# SCH_cansat2025_2025-10-27.net
KiCad netlist of a schematic drawn in EasyEDA
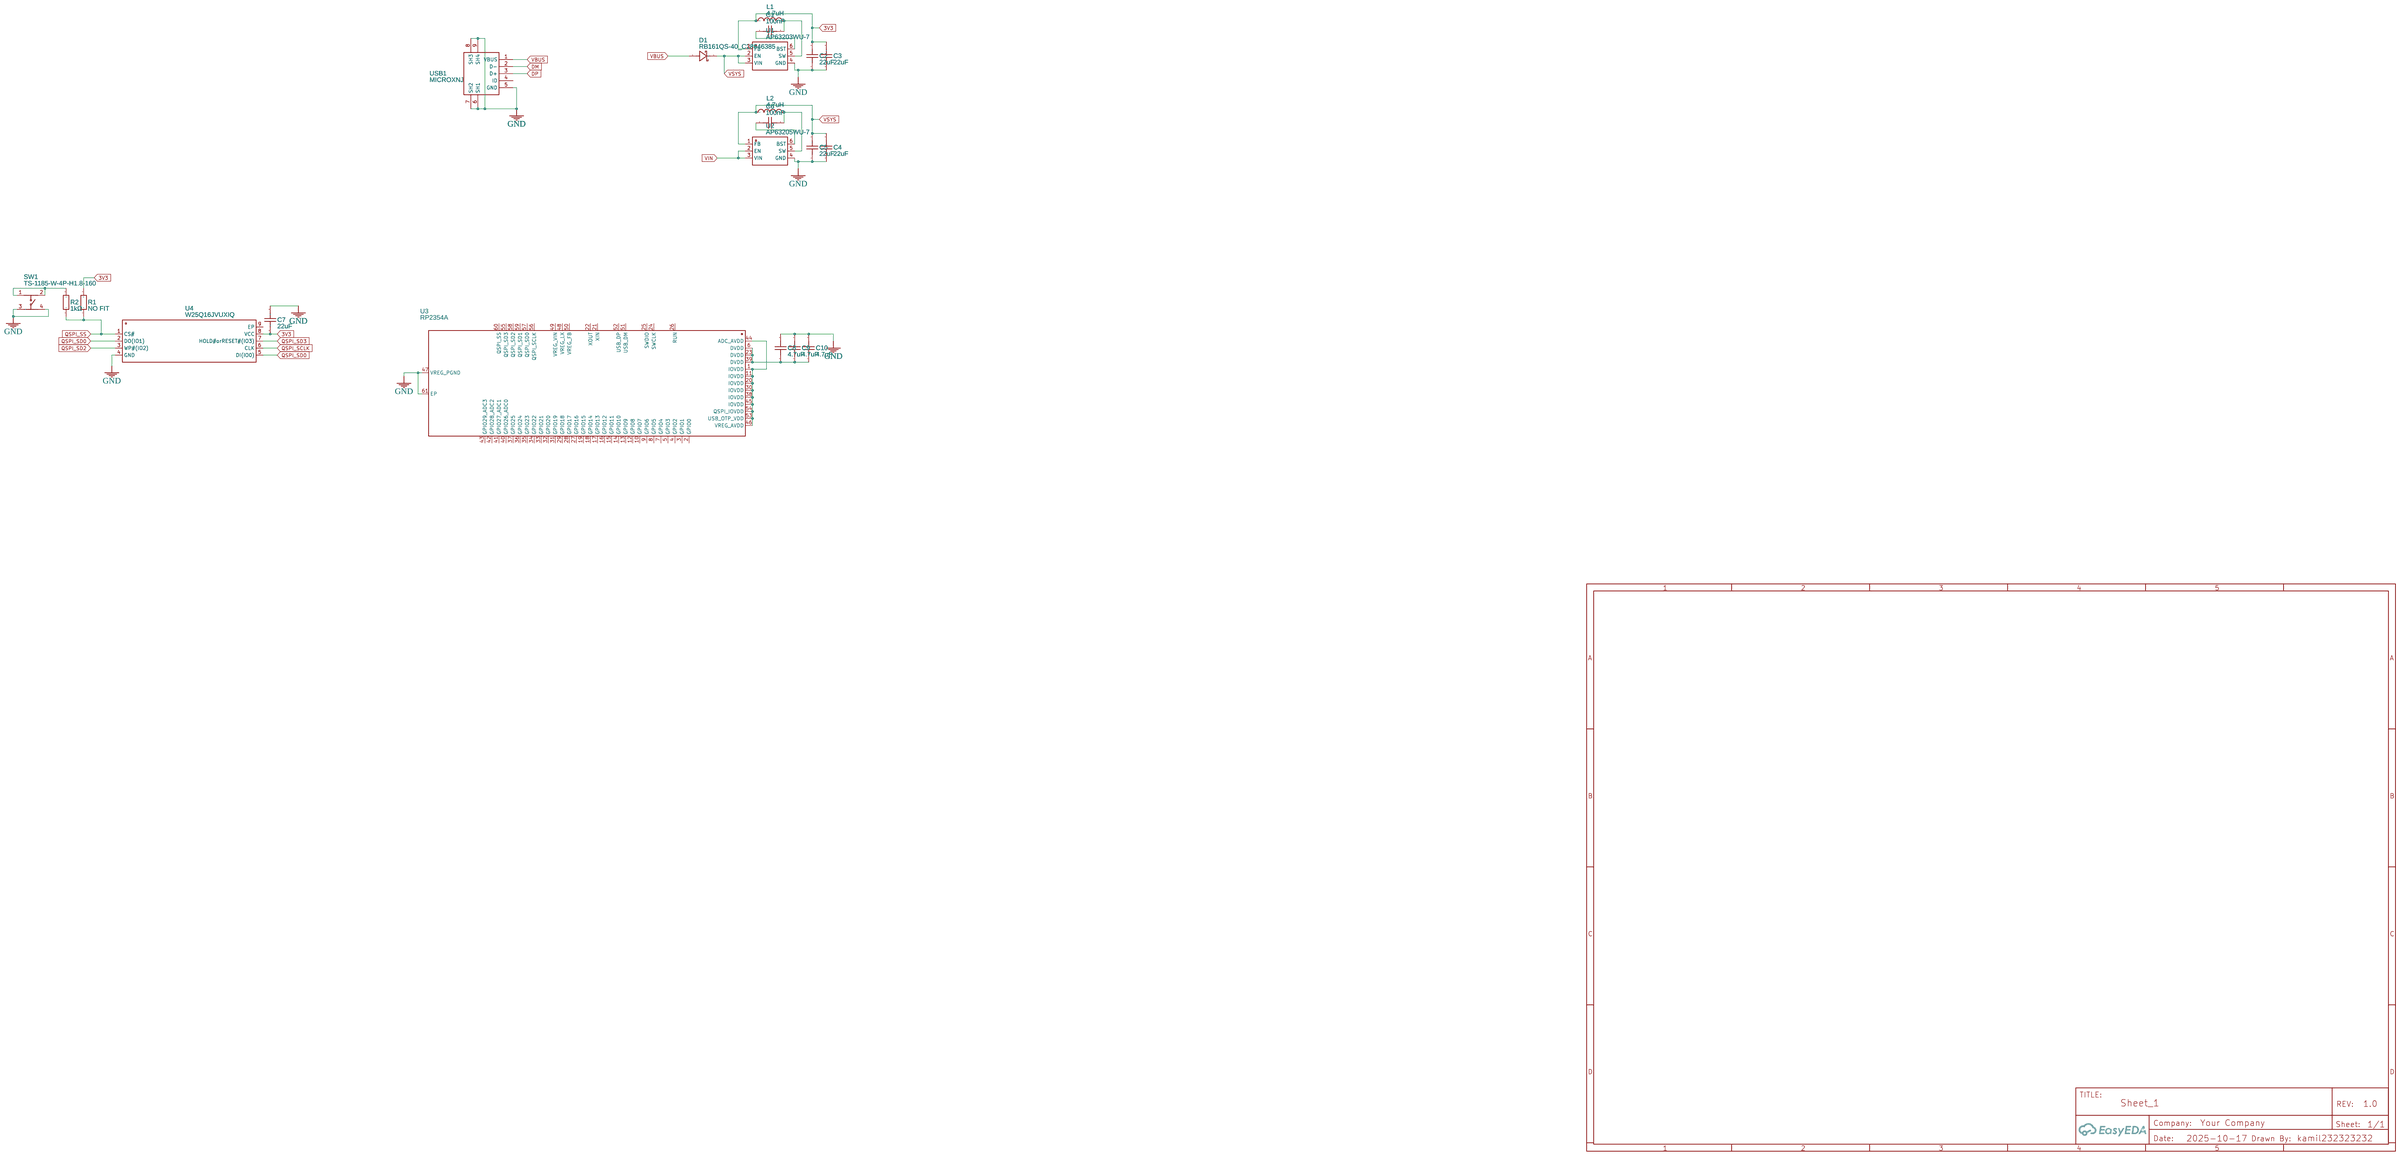
[diagram p0: schematic sheet]

(export (version "E")
  (design (tool "Eeschema 10.0.6"))
  (components
    (comp (ref "C1")
      (value "100nF")
      (fields
        (field (name "Manufacturer Part") "FCC0402B104K160AT")
        (field (name "Manufacturer") "FOJAN(富捷)")
      )
      (libsource (lib "") (part "FCC0402B104K160AT"))
    )
    (comp (ref "C2")
      (value "22uF")
      (fields
        (field (name "Manufacturer Part") "GRM155R60J226ME11D")
        (field (name "Manufacturer") "muRata(村田)")
      )
      (libsource (lib "") (part "GRM155R60J226ME11D"))
    )
    (comp (ref "C3")
      (value "22uF")
      (fields
        (field (name "Manufacturer Part") "GRM155R60J226ME11D")
        (field (name "Manufacturer") "muRata(村田)")
      )
      (libsource (lib "") (part "GRM155R60J226ME11D"))
    )
    (comp (ref "C4")
      (value "22uF")
      (fields
        (field (name "Manufacturer Part") "GRM155R60J226ME11D")
        (field (name "Manufacturer") "muRata(村田)")
      )
      (libsource (lib "") (part "GRM155R60J226ME11D"))
    )
    (comp (ref "C5")
      (value "22uF")
      (fields
        (field (name "Manufacturer Part") "GRM155R60J226ME11D")
        (field (name "Manufacturer") "muRata(村田)")
      )
      (libsource (lib "") (part "GRM155R60J226ME11D"))
    )
    (comp (ref "C6")
      (value "100nF")
      (fields
        (field (name "Manufacturer Part") "FCC0402B104K160AT")
        (field (name "Manufacturer") "FOJAN(富捷)")
      )
      (libsource (lib "") (part "FCC0402B104K160AT"))
    )
    (comp (ref "C7")
      (value "22uF")
      (fields
        (field (name "Manufacturer Part") "GRM155R60J226ME11D")
        (field (name "Manufacturer") "muRata(村田)")
      )
      (libsource (lib "") (part "GRM155R60J226ME11D"))
    )
    (comp (ref "C8")
      (value "4.7uF")
      (fields
        (field (name "Manufacturer Part") "CL05A475MP5NRNC")
        (field (name "Manufacturer") "SAMSUNG(三星)")
      )
      (libsource (lib "") (part "CL05A475MP5NRNC"))
    )
    (comp (ref "C9")
      (value "4.7uF")
      (fields
        (field (name "Manufacturer Part") "CL05A475MP5NRNC")
        (field (name "Manufacturer") "SAMSUNG(三星)")
      )
      (libsource (lib "") (part "CL05A475MP5NRNC"))
    )
    (comp (ref "C10")
      (value "4.7uF")
      (fields
        (field (name "Manufacturer Part") "CL05A475MP5NRNC")
        (field (name "Manufacturer") "SAMSUNG(三星)")
      )
      (libsource (lib "") (part "CL05A475MP5NRNC"))
    )
    (comp (ref "D1")
      (value "RB161QS-40_C28646385")
      (fields (field (name "Manufacturer Part") "RB161QS-40") (field (name "Manufacturer") "TECH PUBLIC(台舟)"))
      (libsource (lib "") (part "RB161QS-40_C28646385"))
    )
    (comp (ref "L1")
      (value "4.7uH")
      (fields (field (name "Manufacturer Part") "CMI201209U4R7KT") (field (name "Manufacturer") "FH(风华)"))
      (libsource (lib "") (part "CMI201209U4R7KT"))
    )
    (comp (ref "L2")
      (value "4.7uH")
      (fields (field (name "Manufacturer Part") "CMI201209U4R7KT") (field (name "Manufacturer") "FH(风华)"))
      (libsource (lib "") (part "CMI201209U4R7KT_1"))
    )
    (comp (ref "R1")
      (value "NO FIT")
      (fields
        (field (name "Manufacturer Part") "0402WGF1002TCE")
        (field (name "Manufacturer") "UNI-ROYAL(厚声)")
      )
      (libsource (lib "") (part "0402WGF1002TCE"))
    )
    (comp (ref "R2")
      (value "1kΩ")
      (fields
        (field (name "Manufacturer Part") "0402WGF1001TCE")
        (field (name "Manufacturer") "UNI-ROYAL(厚声)")
      )
      (libsource (lib "") (part "0402WGF1001TCE"))
    )
    (comp (ref "SW1")
      (value "TS-1185-W-4P-H1.8-160")
      (fields (field (name "Manufacturer") "CAX(创都)"))
      (libsource (lib "") (part "TS-1185-W-4P-H1.8-160"))
    )
    (comp (ref "U1")
      (value "AP63203WU-7")
      (fields (field (name "Manufacturer") "DIODES(美台)"))
      (libsource (lib "") (part "AP63203WU-7"))
    )
    (comp (ref "U2")
      (value "AP63205WU-7")
      (fields (field (name "Manufacturer") "DIODES(美台)"))
      (libsource (lib "") (part "AP63205WU-7"))
    )
    (comp (ref "U3")
      (value "RP2354A")
      (fields (field (name "Manufacturer") "Raspberry Pi(树莓派)"))
      (libsource (lib "") (part "RP2354A"))
    )
    (comp (ref "U4")
      (value "W25Q16JVUXIQ")
      (fields (field (name "Manufacturer") "Winbond(华邦)"))
      (libsource (lib "") (part "W25Q16JVUXIQ"))
    )
    (comp (ref "USB1")
      (value "MICROXNJ")
      (fields (field (name "Manufacturer Part") "MicroXNJ") (field (name "Manufacturer") "SHOU HAN(首韩)"))
      (libsource (lib "") (part "MICROXNJ"))
    )
  )
  (nets
    (net (code "1") (name "3V3") (class "Default")
      (node (ref "C2") (pin "2") (pinfunction "2_2") (pintype "unspecified"))
      (node (ref "C3") (pin "2") (pinfunction "2_2") (pintype "unspecified"))
      (node (ref "C7") (pin "1") (pinfunction "1_1") (pintype "unspecified"))
      (node (ref "L1") (pin "1") (pinfunction "1_1") (pintype "unspecified"))
      (node (ref "R1") (pin "2") (pinfunction "2_2") (pintype "input"))
      (node (ref "U1") (pin "1") (pinfunction "FB_1") (pintype "unspecified"))
      (node (ref "U4") (pin "8") (pinfunction "VCC_8") (pintype "unspecified"))
    )
    (net (code "2") (name "DM") (class "Default")
      (node (ref "USB1") (pin "2") (pinfunction "D-_2") (pintype "unspecified"))
    )
    (net (code "3") (name "DP") (class "Default")
      (node (ref "USB1") (pin "3") (pinfunction "D+_3") (pintype "unspecified"))
    )
    (net (code "4") (name "GND") (class "Default")
      (node (ref "C10") (pin "2") (pinfunction "2_2") (pintype "unspecified"))
      (node (ref "C2") (pin "1") (pinfunction "1_1") (pintype "unspecified"))
      (node (ref "C3") (pin "1") (pinfunction "1_1") (pintype "unspecified"))
      (node (ref "C4") (pin "1") (pinfunction "1_1") (pintype "unspecified"))
      (node (ref "C5") (pin "1") (pinfunction "1_1") (pintype "unspecified"))
      (node (ref "C7") (pin "2") (pinfunction "2_2") (pintype "unspecified"))
      (node (ref "C8") (pin "2") (pinfunction "2_2") (pintype "unspecified"))
      (node (ref "C9") (pin "2") (pinfunction "2_2") (pintype "unspecified"))
      (node (ref "SW1") (pin "3") (pinfunction "3_3") (pintype "unspecified"))
      (node (ref "SW1") (pin "4") (pinfunction "4_4") (pintype "unspecified"))
      (node (ref "U1") (pin "4") (pinfunction "GND_4") (pintype "unspecified"))
      (node (ref "U2") (pin "4") (pinfunction "GND_4") (pintype "unspecified"))
      (node (ref "U3") (pin "47") (pinfunction "VREG_PGND_47") (pintype "unspecified"))
      (node (ref "U3") (pin "61") (pinfunction "EP_61") (pintype "unspecified"))
      (node (ref "U4") (pin "4") (pinfunction "GND_4") (pintype "unspecified"))
      (node (ref "USB1") (pin "5") (pinfunction "GND_5") (pintype "unspecified"))
      (node (ref "USB1") (pin "6") (pinfunction "SH1_6") (pintype "unspecified"))
      (node (ref "USB1") (pin "7") (pinfunction "SH2_7") (pintype "unspecified"))
      (node (ref "USB1") (pin "8") (pinfunction "SH3_8") (pintype "unspecified"))
      (node (ref "USB1") (pin "9") (pinfunction "SH4_9") (pintype "unspecified"))
    )
    (net (code "5") (name "Net-(C10-Pad1)") (class "Default")
      (node (ref "C10") (pin "1") (pinfunction "1_1") (pintype "unspecified"))
      (node (ref "C8") (pin "1") (pinfunction "1_1") (pintype "unspecified"))
      (node (ref "C9") (pin "1") (pinfunction "1_1") (pintype "unspecified"))
      (node (ref "U3") (pin "23") (pinfunction "DVDD_23") (pintype "unspecified"))
      (node (ref "U3") (pin "39") (pinfunction "DVDD_39") (pintype "unspecified"))
      (node (ref "U3") (pin "6") (pinfunction "DVDD_6") (pintype "unspecified"))
    )
    (net (code "6") (name "Net-(R2-Pad2)") (class "Default")
      (node (ref "R2") (pin "2") (pinfunction "2_2") (pintype "input"))
      (node (ref "SW1") (pin "1") (pinfunction "1_1") (pintype "unspecified"))
      (node (ref "SW1") (pin "2") (pinfunction "2_2") (pintype "unspecified"))
    )
    (net (code "7") (name "Net-(U1-BST)") (class "Default")
      (node (ref "C1") (pin "1") (pinfunction "1_1") (pintype "unspecified"))
      (node (ref "U1") (pin "6") (pinfunction "BST_6") (pintype "unspecified"))
    )
    (net (code "8") (name "Net-(U1-SW)") (class "Default")
      (node (ref "C1") (pin "2") (pinfunction "2_2") (pintype "unspecified"))
      (node (ref "L1") (pin "2") (pinfunction "2_2") (pintype "unspecified"))
      (node (ref "U1") (pin "5") (pinfunction "SW_5") (pintype "unspecified"))
    )
    (net (code "9") (name "Net-(U2-BST)") (class "Default")
      (node (ref "C6") (pin "1") (pinfunction "1_1") (pintype "unspecified"))
      (node (ref "U2") (pin "6") (pinfunction "BST_6") (pintype "unspecified"))
    )
    (net (code "10") (name "Net-(U2-SW)") (class "Default")
      (node (ref "C6") (pin "2") (pinfunction "2_2") (pintype "unspecified"))
      (node (ref "L2") (pin "2") (pinfunction "2_2") (pintype "unspecified"))
      (node (ref "U2") (pin "5") (pinfunction "SW_5") (pintype "unspecified"))
    )
    (net (code "11") (name "Net-(U3-ADC_AVDD)") (class "Default")
      (node (ref "U3") (pin "1") (pinfunction "IOVDD_1") (pintype "unspecified"))
      (node (ref "U3") (pin "11") (pinfunction "IOVDD_11") (pintype "unspecified"))
      (node (ref "U3") (pin "20") (pinfunction "IOVDD_20") (pintype "unspecified"))
      (node (ref "U3") (pin "30") (pinfunction "IOVDD_30") (pintype "unspecified"))
      (node (ref "U3") (pin "38") (pinfunction "IOVDD_38") (pintype "unspecified"))
      (node (ref "U3") (pin "44") (pinfunction "ADC_AVDD_44") (pintype "unspecified"))
      (node (ref "U3") (pin "45") (pinfunction "IOVDD_45") (pintype "unspecified"))
      (node (ref "U3") (pin "46") (pinfunction "VREG_AVDD_46") (pintype "unspecified"))
      (node (ref "U3") (pin "53") (pinfunction "USB_OTP_VDD_53") (pintype "unspecified"))
      (node (ref "U3") (pin "54") (pinfunction "QSPI_IOVDD_54") (pintype "unspecified"))
    )
    (net (code "12") (name "QSPI_SCLK") (class "Default")
      (node (ref "U4") (pin "6") (pinfunction "CLK_6") (pintype "unspecified"))
    )
    (net (code "13") (name "QSPI_SD0") (class "Default")
      (node (ref "U4") (pin "2") (pinfunction "DO(IO1)_2") (pintype "unspecified"))
      (node (ref "U4") (pin "5") (pinfunction "DI(IO0)_5") (pintype "unspecified"))
    )
    (net (code "14") (name "QSPI_SD2") (class "Default")
      (node (ref "U4") (pin "3") (pinfunction "WP#(IO2)_3") (pintype "unspecified"))
    )
    (net (code "15") (name "QSPI_SD3") (class "Default")
      (node (ref "U4") (pin "7") (pinfunction "HOLD#orRESET#(IO3)_7") (pintype "unspecified"))
    )
    (net (code "16") (name "QSPI_SS") (class "Default")
      (node (ref "R1") (pin "1") (pinfunction "1_1") (pintype "input"))
      (node (ref "R2") (pin "1") (pinfunction "1_1") (pintype "input"))
      (node (ref "U4") (pin "1") (pinfunction "CS#_1") (pintype "unspecified"))
    )
    (net (code "17") (name "VBUS") (class "Default")
      (node (ref "D1") (pin "2") (pinfunction "A_2") (pintype "unspecified"))
      (node (ref "USB1") (pin "1") (pinfunction "VBUS_1") (pintype "unspecified"))
    )
    (net (code "18") (name "VIN") (class "Default")
      (node (ref "U2") (pin "2") (pinfunction "EN_2") (pintype "unspecified"))
      (node (ref "U2") (pin "3") (pinfunction "VIN_3") (pintype "unspecified"))
    )
    (net (code "19") (name "VSYS") (class "Default")
      (node (ref "C4") (pin "2") (pinfunction "2_2") (pintype "unspecified"))
      (node (ref "C5") (pin "2") (pinfunction "2_2") (pintype "unspecified"))
      (node (ref "D1") (pin "1") (pinfunction "C_1") (pintype "unspecified"))
      (node (ref "L2") (pin "1") (pinfunction "1_1") (pintype "unspecified"))
      (node (ref "U1") (pin "2") (pinfunction "EN_2") (pintype "unspecified"))
      (node (ref "U1") (pin "3") (pinfunction "VIN_3") (pintype "unspecified"))
      (node (ref "U2") (pin "1") (pinfunction "FB_1") (pintype "unspecified"))
    )
    (net (code "20") (name "unconnected-(U3-GPIO0-Pad2)") (class "Default")
      (node (ref "U3") (pin "2") (pinfunction "GPIO0_2") (pintype "unspecified"))
    )
    (net (code "21") (name "unconnected-(U3-GPIO1-Pad3)") (class "Default")
      (node (ref "U3") (pin "3") (pinfunction "GPIO1_3") (pintype "unspecified"))
    )
    (net (code "22") (name "unconnected-(U3-GPIO2-Pad4)") (class "Default")
      (node (ref "U3") (pin "4") (pinfunction "GPIO2_4") (pintype "unspecified"))
    )
    (net (code "23") (name "unconnected-(U3-GPIO3-Pad5)") (class "Default")
      (node (ref "U3") (pin "5") (pinfunction "GPIO3_5") (pintype "unspecified"))
    )
    (net (code "24") (name "unconnected-(U3-GPIO4-Pad7)") (class "Default")
      (node (ref "U3") (pin "7") (pinfunction "GPIO4_7") (pintype "unspecified"))
    )
    (net (code "25") (name "unconnected-(U3-GPIO5-Pad8)") (class "Default")
      (node (ref "U3") (pin "8") (pinfunction "GPIO5_8") (pintype "unspecified"))
    )
    (net (code "26") (name "unconnected-(U3-GPIO6-Pad9)") (class "Default")
      (node (ref "U3") (pin "9") (pinfunction "GPIO6_9") (pintype "unspecified"))
    )
    (net (code "27") (name "unconnected-(U3-GPIO7-Pad10)") (class "Default")
      (node (ref "U3") (pin "10") (pinfunction "GPIO7_10") (pintype "unspecified"))
    )
    (net (code "28") (name "unconnected-(U3-GPIO8-Pad12)") (class "Default")
      (node (ref "U3") (pin "12") (pinfunction "GPIO8_12") (pintype "unspecified"))
    )
    (net (code "29") (name "unconnected-(U3-GPIO9-Pad13)") (class "Default")
      (node (ref "U3") (pin "13") (pinfunction "GPIO9_13") (pintype "unspecified"))
    )
    (net (code "30") (name "unconnected-(U3-GPIO10-Pad14)") (class "Default")
      (node (ref "U3") (pin "14") (pinfunction "GPIO10_14") (pintype "unspecified"))
    )
    (net (code "31") (name "unconnected-(U3-GPIO11-Pad15)") (class "Default")
      (node (ref "U3") (pin "15") (pinfunction "GPIO11_15") (pintype "unspecified"))
    )
    (net (code "32") (name "unconnected-(U3-GPIO12-Pad16)") (class "Default")
      (node (ref "U3") (pin "16") (pinfunction "GPIO12_16") (pintype "unspecified"))
    )
    (net (code "33") (name "unconnected-(U3-GPIO13-Pad17)") (class "Default")
      (node (ref "U3") (pin "17") (pinfunction "GPIO13_17") (pintype "unspecified"))
    )
    (net (code "34") (name "unconnected-(U3-GPIO14-Pad18)") (class "Default")
      (node (ref "U3") (pin "18") (pinfunction "GPIO14_18") (pintype "unspecified"))
    )
    (net (code "35") (name "unconnected-(U3-GPIO15-Pad19)") (class "Default")
      (node (ref "U3") (pin "19") (pinfunction "GPIO15_19") (pintype "unspecified"))
    )
    (net (code "36") (name "unconnected-(U3-GPIO16-Pad27)") (class "Default")
      (node (ref "U3") (pin "27") (pinfunction "GPIO16_27") (pintype "unspecified"))
    )
    (net (code "37") (name "unconnected-(U3-GPIO17-Pad28)") (class "Default")
      (node (ref "U3") (pin "28") (pinfunction "GPIO17_28") (pintype "unspecified"))
    )
    (net (code "38") (name "unconnected-(U3-GPIO18-Pad29)") (class "Default")
      (node (ref "U3") (pin "29") (pinfunction "GPIO18_29") (pintype "unspecified"))
    )
    (net (code "39") (name "unconnected-(U3-GPIO19-Pad31)") (class "Default")
      (node (ref "U3") (pin "31") (pinfunction "GPIO19_31") (pintype "unspecified"))
    )
    (net (code "40") (name "unconnected-(U3-GPIO20-Pad32)") (class "Default")
      (node (ref "U3") (pin "32") (pinfunction "GPIO20_32") (pintype "unspecified"))
    )
    (net (code "41") (name "unconnected-(U3-GPIO21-Pad33)") (class "Default")
      (node (ref "U3") (pin "33") (pinfunction "GPIO21_33") (pintype "unspecified"))
    )
    (net (code "42") (name "unconnected-(U3-GPIO22-Pad34)") (class "Default")
      (node (ref "U3") (pin "34") (pinfunction "GPIO22_34") (pintype "unspecified"))
    )
    (net (code "43") (name "unconnected-(U3-GPIO23-Pad35)") (class "Default")
      (node (ref "U3") (pin "35") (pinfunction "GPIO23_35") (pintype "unspecified"))
    )
    (net (code "44") (name "unconnected-(U3-GPIO24-Pad36)") (class "Default")
      (node (ref "U3") (pin "36") (pinfunction "GPIO24_36") (pintype "unspecified"))
    )
    (net (code "45") (name "unconnected-(U3-GPIO25-Pad37)") (class "Default")
      (node (ref "U3") (pin "37") (pinfunction "GPIO25_37") (pintype "unspecified"))
    )
    (net (code "46") (name "unconnected-(U3-GPIO26_ADC0-Pad40)") (class "Default")
      (node (ref "U3") (pin "40") (pinfunction "GPIO26_ADC0_40") (pintype "unspecified"))
    )
    (net (code "47") (name "unconnected-(U3-GPIO27_ADC1-Pad41)") (class "Default")
      (node (ref "U3") (pin "41") (pinfunction "GPIO27_ADC1_41") (pintype "unspecified"))
    )
    (net (code "48") (name "unconnected-(U3-GPIO28_ADC2-Pad42)") (class "Default")
      (node (ref "U3") (pin "42") (pinfunction "GPIO28_ADC2_42") (pintype "unspecified"))
    )
    (net (code "49") (name "unconnected-(U3-GPIO29_ADC3-Pad43)") (class "Default")
      (node (ref "U3") (pin "43") (pinfunction "GPIO29_ADC3_43") (pintype "unspecified"))
    )
    (net (code "50") (name "unconnected-(U3-QSPI_SCLK-Pad56)") (class "Default")
      (node (ref "U3") (pin "56") (pinfunction "QSPI_SCLK_56") (pintype "unspecified"))
    )
    (net (code "51") (name "unconnected-(U3-QSPI_SD0-Pad57)") (class "Default")
      (node (ref "U3") (pin "57") (pinfunction "QSPI_SD0_57") (pintype "unspecified"))
    )
    (net (code "52") (name "unconnected-(U3-QSPI_SD1-Pad59)") (class "Default")
      (node (ref "U3") (pin "59") (pinfunction "QSPI_SD1_59") (pintype "unspecified"))
    )
    (net (code "53") (name "unconnected-(U3-QSPI_SD2-Pad58)") (class "Default")
      (node (ref "U3") (pin "58") (pinfunction "QSPI_SD2_58") (pintype "unspecified"))
    )
    (net (code "54") (name "unconnected-(U3-QSPI_SD3-Pad55)") (class "Default")
      (node (ref "U3") (pin "55") (pinfunction "QSPI_SD3_55") (pintype "unspecified"))
    )
    (net (code "55") (name "unconnected-(U3-QSPI_SS-Pad60)") (class "Default")
      (node (ref "U3") (pin "60") (pinfunction "QSPI_SS_60") (pintype "unspecified"))
    )
    (net (code "56") (name "unconnected-(U3-RUN-Pad26)") (class "Default")
      (node (ref "U3") (pin "26") (pinfunction "RUN_26") (pintype "unspecified"))
    )
    (net (code "57") (name "unconnected-(U3-SWCLK-Pad24)") (class "Default")
      (node (ref "U3") (pin "24") (pinfunction "SWCLK_24") (pintype "unspecified"))
    )
    (net (code "58") (name "unconnected-(U3-SWDIO-Pad25)") (class "Default")
      (node (ref "U3") (pin "25") (pinfunction "SWDIO_25") (pintype "unspecified"))
    )
    (net (code "59") (name "unconnected-(U3-USB_DM-Pad51)") (class "Default")
      (node (ref "U3") (pin "51") (pinfunction "USB_DM_51") (pintype "unspecified"))
    )
    (net (code "60") (name "unconnected-(U3-USB_DP-Pad52)") (class "Default")
      (node (ref "U3") (pin "52") (pinfunction "USB_DP_52") (pintype "unspecified"))
    )
    (net (code "61") (name "unconnected-(U3-VREG_FB-Pad50)") (class "Default")
      (node (ref "U3") (pin "50") (pinfunction "VREG_FB_50") (pintype "unspecified"))
    )
    (net (code "62") (name "unconnected-(U3-VREG_LX-Pad48)") (class "Default")
      (node (ref "U3") (pin "48") (pinfunction "VREG_LX_48") (pintype "unspecified"))
    )
    (net (code "63") (name "unconnected-(U3-VREG_VIN-Pad49)") (class "Default")
      (node (ref "U3") (pin "49") (pinfunction "VREG_VIN_49") (pintype "unspecified"))
    )
    (net (code "64") (name "unconnected-(U3-XIN-Pad21)") (class "Default")
      (node (ref "U3") (pin "21") (pinfunction "XIN_21") (pintype "unspecified"))
    )
    (net (code "65") (name "unconnected-(U3-XOUT-Pad22)") (class "Default")
      (node (ref "U3") (pin "22") (pinfunction "XOUT_22") (pintype "unspecified"))
    )
    (net (code "66") (name "unconnected-(U4-EP-Pad9)") (class "Default")
      (node (ref "U4") (pin "9") (pinfunction "EP_9") (pintype "unspecified"))
    )
    (net (code "67") (name "unconnected-(USB1-ID-Pad4)") (class "Default")
      (node (ref "USB1") (pin "4") (pinfunction "ID_4") (pintype "unspecified"))
    )
  )
)
